# Group12_411_REV0.net
KiCad netlist of a schematic drawn in EAGLE
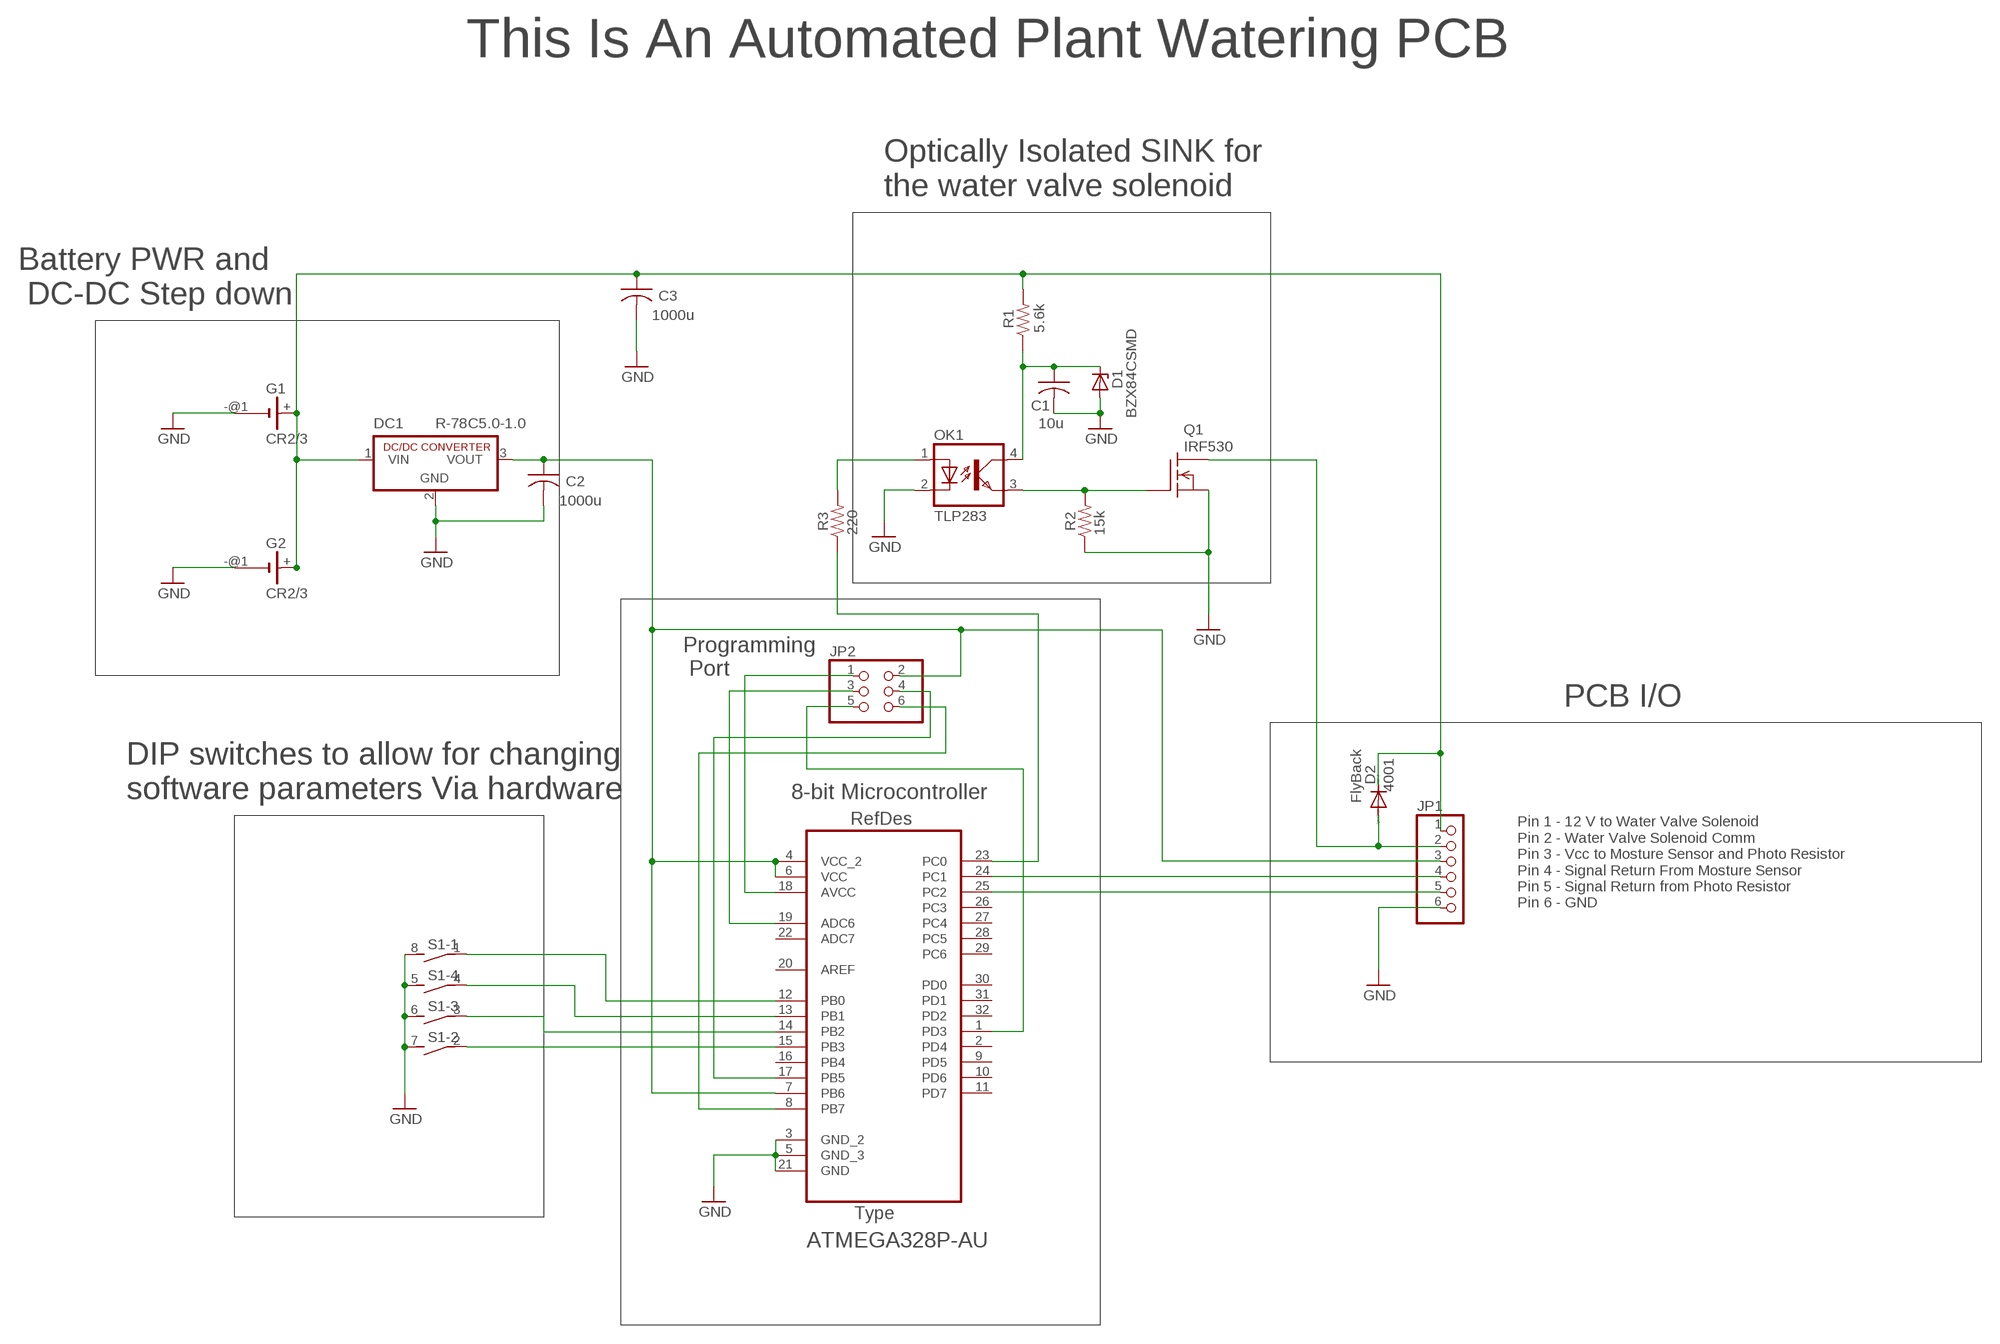
[diagram p0: schematic, sheet 1]

(export (version "E")
  (design (tool "Eeschema 10.0.6"))
  (components
    (comp (ref "ATMEGA328")
      (value "ATMEGA328P-AU")
      (footprint "eagle-import:QFP80P900X900X120-32N")
      (description "8-bit Microcontroller")
      (fields (field (name "MPN") "ATMEGA328P-AU"))
      (libsource (lib "eagle-import") (part "ATMEGA328P-AU"))
    )
    (comp (ref "C1")
      (value "C-USC0805")
      (footprint "eagle-import:C0805")
      (fields (field (name "C") "10u"))
      (libsource (lib "eagle-import") (part "C-USC0805"))
    )
    (comp (ref "C2")
      (value "C-USC0805")
      (footprint "eagle-import:C0805")
      (fields (field (name "C") "1000u"))
      (libsource (lib "eagle-import") (part "C-USC0805"))
    )
    (comp (ref "C3")
      (value "C-USC0805")
      (footprint "eagle-import:C0805")
      (fields (field (name "C") "1000u"))
      (libsource (lib "eagle-import") (part "C-USC0805"))
    )
    (comp (ref "D1")
      (value "BZX84CSMD")
      (footprint "eagle-import:TO236")
      (libsource (lib "eagle-import") (part "BZX84CSMD"))
    )
    (comp (ref "D2")
      (value "ES2D")
      (footprint "eagle-import:SMB")
      (fields (field (name "D") "4001"))
      (libsource (lib "eagle-import") (part "ES2D"))
    )
    (comp (ref "DC1")
      (value "R-78C5.0-1.0")
      (footprint "eagle-import:SIP3")
      (libsource (lib "eagle-import") (part "R-78C-1.05.0"))
    )
    (comp (ref "G1")
      (value "CR2/3")
      (footprint "eagle-import:CR2_3")
      (libsource (lib "eagle-import") (part "CR2/3"))
    )
    (comp (ref "G2")
      (value "CR2/3")
      (footprint "eagle-import:CR2_3")
      (libsource (lib "eagle-import") (part "CR2/3"))
    )
    (comp (ref "JP1")
      (value "PINHD-1X6")
      (footprint "eagle-import:1X06")
      (libsource (lib "eagle-import") (part "PINHD-1X6"))
    )
    (comp (ref "JP2")
      (value "PINHD-2X3")
      (footprint "eagle-import:2X03")
      (libsource (lib "eagle-import") (part "PINHD-2X3"))
    )
    (comp (ref "OK1")
      (value "TLP283")
      (footprint "eagle-import:MINI-FLAT-4")
      (libsource (lib "eagle-import") (part "TLP283"))
    )
    (comp (ref "Q1")
      (value "VN66AF")
      (footprint "eagle-import:TO202")
      (fields (field (name "NPN") "IRF530"))
      (libsource (lib "eagle-import") (part "VN66AF"))
    )
    (comp (ref "R1")
      (value "R-US_M0805")
      (footprint "eagle-import:M0805")
      (fields (field (name "R") "5.6k"))
      (libsource (lib "eagle-import") (part "R-US_M0805"))
    )
    (comp (ref "R2")
      (value "R-US_M0805")
      (footprint "eagle-import:M0805")
      (fields (field (name "R") "15k"))
      (libsource (lib "eagle-import") (part "R-US_M0805"))
    )
    (comp (ref "R3")
      (value "R-US_M0805")
      (footprint "eagle-import:M0805")
      (fields (field (name "R") "220"))
      (libsource (lib "eagle-import") (part "R-US_M0805"))
    )
    (comp (ref "S1")
      (value "DIP04S")
      (footprint "eagle-import:DIP04S")
      (libsource (lib "eagle-import") (part "DIP04S"))
    )
  )
  (nets
    (net (code "1") (name "GND") (class "Default")
      (node (ref "ATMEGA328") (pin "21") (pinfunction "GND_21") (pintype "passive"))
      (node (ref "ATMEGA328") (pin "3") (pinfunction "GND_2_3") (pintype "passive"))
      (node (ref "ATMEGA328") (pin "5") (pinfunction "GND_3_5") (pintype "passive"))
      (node (ref "C1") (pin "2") (pinfunction "2_2") (pintype "passive"))
      (node (ref "C2") (pin "2") (pinfunction "2_2") (pintype "passive"))
      (node (ref "C3") (pin "2") (pinfunction "2_2") (pintype "passive"))
      (node (ref "D1") (pin "A") (pinfunction "A_A") (pintype "passive"))
      (node (ref "DC1") (pin "2") (pinfunction "GND_2") (pintype "passive"))
      (node (ref "G1") (pin "-@1") (pinfunction "-_-@1") (pintype "passive"))
      (node (ref "G2") (pin "-@1") (pinfunction "-_-@1") (pintype "passive"))
      (node (ref "JP1") (pin "6") (pinfunction "6_6") (pintype "passive"))
      (node (ref "OK1") (pin "2") (pinfunction "C_2") (pintype "passive"))
      (node (ref "Q1") (pin "1") (pinfunction "S_1") (pintype "passive"))
      (node (ref "R2") (pin "1") (pinfunction "1_1") (pintype "passive"))
      (node (ref "S1") (pin "5") (pinfunction "2_5") (pintype "passive"))
      (node (ref "S1") (pin "6") (pinfunction "2_6") (pintype "passive"))
      (node (ref "S1") (pin "7") (pinfunction "2_7") (pintype "passive"))
      (node (ref "S1") (pin "8") (pinfunction "2_8") (pintype "passive"))
    )
    (net (code "2") (name "Net-(ATMEGA328-ADC6)") (class "Default")
      (node (ref "ATMEGA328") (pin "19") (pinfunction "ADC6_19") (pintype "input"))
      (node (ref "JP2") (pin "3") (pinfunction "3_3") (pintype "passive"))
    )
    (net (code "3") (name "Net-(ATMEGA328-AVCC)") (class "Default")
      (node (ref "ATMEGA328") (pin "18") (pinfunction "AVCC_18") (pintype "power_in"))
      (node (ref "JP2") (pin "1") (pinfunction "1_1") (pintype "passive"))
    )
    (net (code "4") (name "Net-(ATMEGA328-PB0)") (class "Default")
      (node (ref "ATMEGA328") (pin "12") (pinfunction "PB0_12") (pintype "bidirectional"))
      (node (ref "S1") (pin "1") (pinfunction "1_1") (pintype "passive"))
    )
    (net (code "5") (name "Net-(ATMEGA328-PB1)") (class "Default")
      (node (ref "ATMEGA328") (pin "13") (pinfunction "PB1_13") (pintype "bidirectional"))
      (node (ref "S1") (pin "4") (pinfunction "1_4") (pintype "passive"))
    )
    (net (code "6") (name "Net-(ATMEGA328-PB2)") (class "Default")
      (node (ref "ATMEGA328") (pin "14") (pinfunction "PB2_14") (pintype "bidirectional"))
      (node (ref "S1") (pin "3") (pinfunction "1_3") (pintype "passive"))
    )
    (net (code "7") (name "Net-(ATMEGA328-PB3)") (class "Default")
      (node (ref "ATMEGA328") (pin "15") (pinfunction "PB3_15") (pintype "bidirectional"))
      (node (ref "S1") (pin "2") (pinfunction "1_2") (pintype "passive"))
    )
    (net (code "8") (name "Net-(ATMEGA328-PB5)") (class "Default")
      (node (ref "ATMEGA328") (pin "17") (pinfunction "PB5_17") (pintype "bidirectional"))
      (node (ref "JP2") (pin "4") (pinfunction "4_4") (pintype "passive"))
    )
    (net (code "9") (name "Net-(ATMEGA328-PB6)") (class "Default")
      (node (ref "ATMEGA328") (pin "4") (pinfunction "VCC_2_4") (pintype "power_in"))
      (node (ref "ATMEGA328") (pin "6") (pinfunction "VCC_6") (pintype "power_in"))
      (node (ref "ATMEGA328") (pin "7") (pinfunction "PB6_7") (pintype "bidirectional"))
      (node (ref "C2") (pin "1") (pinfunction "1_1") (pintype "passive"))
      (node (ref "DC1") (pin "3") (pinfunction "VOUT_3") (pintype "passive"))
      (node (ref "JP1") (pin "3") (pinfunction "3_3") (pintype "passive"))
      (node (ref "JP2") (pin "2") (pinfunction "2_2") (pintype "passive"))
    )
    (net (code "10") (name "Net-(ATMEGA328-PB7)") (class "Default")
      (node (ref "ATMEGA328") (pin "8") (pinfunction "PB7_8") (pintype "bidirectional"))
      (node (ref "JP2") (pin "6") (pinfunction "6_6") (pintype "passive"))
    )
    (net (code "11") (name "Net-(ATMEGA328-PC0)") (class "Default")
      (node (ref "ATMEGA328") (pin "23") (pinfunction "PC0_23") (pintype "bidirectional"))
      (node (ref "R3") (pin "1") (pinfunction "1_1") (pintype "passive"))
    )
    (net (code "12") (name "Net-(ATMEGA328-PC1)") (class "Default")
      (node (ref "ATMEGA328") (pin "24") (pinfunction "PC1_24") (pintype "bidirectional"))
      (node (ref "JP1") (pin "4") (pinfunction "4_4") (pintype "passive"))
    )
    (net (code "13") (name "Net-(ATMEGA328-PC2)") (class "Default")
      (node (ref "ATMEGA328") (pin "25") (pinfunction "PC2_25") (pintype "bidirectional"))
      (node (ref "JP1") (pin "5") (pinfunction "5_5") (pintype "passive"))
    )
    (net (code "14") (name "Net-(ATMEGA328-PD3)") (class "Default")
      (node (ref "ATMEGA328") (pin "1") (pinfunction "PD3_1") (pintype "bidirectional"))
      (node (ref "JP2") (pin "5") (pinfunction "5_5") (pintype "passive"))
    )
    (net (code "15") (name "Net-(DC1-VIN)") (class "Default")
      (node (ref "C3") (pin "1") (pinfunction "1_1") (pintype "passive"))
      (node (ref "D2") (pin "C") (pinfunction "C_C") (pintype "passive"))
      (node (ref "DC1") (pin "1") (pinfunction "VIN_1") (pintype "passive"))
      (node (ref "G1") (pin "+") (pinfunction "+_+") (pintype "passive"))
      (node (ref "G2") (pin "+") (pinfunction "+_+") (pintype "passive"))
      (node (ref "JP1") (pin "1") (pinfunction "1_1") (pintype "passive"))
      (node (ref "R1") (pin "2") (pinfunction "2_2") (pintype "passive"))
    )
    (net (code "16") (name "Net-(OK1-A)") (class "Default")
      (node (ref "OK1") (pin "1") (pinfunction "A_1") (pintype "passive"))
      (node (ref "R3") (pin "2") (pinfunction "2_2") (pintype "passive"))
    )
    (net (code "17") (name "Net-(OK1-COL)") (class "Default")
      (node (ref "C1") (pin "1") (pinfunction "1_1") (pintype "passive"))
      (node (ref "D1") (pin "C") (pinfunction "C_C") (pintype "passive"))
      (node (ref "OK1") (pin "4") (pinfunction "COL_4") (pintype "passive"))
      (node (ref "R1") (pin "1") (pinfunction "1_1") (pintype "passive"))
    )
    (net (code "18") (name "Net-(OK1-EMIT)") (class "Default")
      (node (ref "OK1") (pin "3") (pinfunction "EMIT_3") (pintype "passive"))
      (node (ref "Q1") (pin "2") (pinfunction "G_2") (pintype "passive"))
      (node (ref "R2") (pin "2") (pinfunction "2_2") (pintype "passive"))
    )
    (net (code "19") (name "Net-(Q1-D)") (class "Default")
      (node (ref "D2") (pin "A") (pinfunction "A_A") (pintype "passive"))
      (node (ref "JP1") (pin "2") (pinfunction "2_2") (pintype "passive"))
      (node (ref "Q1") (pin "3") (pinfunction "D_3") (pintype "passive"))
    )
    (net (code "20") (name "unconnected-(ATMEGA328-ADC7-Pad22)") (class "Default")
      (node (ref "ATMEGA328") (pin "22") (pinfunction "ADC7_22") (pintype "input"))
    )
    (net (code "21") (name "unconnected-(ATMEGA328-AREF-Pad20)") (class "Default")
      (node (ref "ATMEGA328") (pin "20") (pinfunction "AREF_20") (pintype "input"))
    )
    (net (code "22") (name "unconnected-(ATMEGA328-PB4-Pad16)") (class "Default")
      (node (ref "ATMEGA328") (pin "16") (pinfunction "PB4_16") (pintype "bidirectional"))
    )
    (net (code "23") (name "unconnected-(ATMEGA328-PC3-Pad26)") (class "Default")
      (node (ref "ATMEGA328") (pin "26") (pinfunction "PC3_26") (pintype "bidirectional"))
    )
    (net (code "24") (name "unconnected-(ATMEGA328-PC4-Pad27)") (class "Default")
      (node (ref "ATMEGA328") (pin "27") (pinfunction "PC4_27") (pintype "bidirectional"))
    )
    (net (code "25") (name "unconnected-(ATMEGA328-PC5-Pad28)") (class "Default")
      (node (ref "ATMEGA328") (pin "28") (pinfunction "PC5_28") (pintype "bidirectional"))
    )
    (net (code "26") (name "unconnected-(ATMEGA328-PC6-Pad29)") (class "Default")
      (node (ref "ATMEGA328") (pin "29") (pinfunction "PC6_29") (pintype "bidirectional"))
    )
    (net (code "27") (name "unconnected-(ATMEGA328-PD0-Pad30)") (class "Default")
      (node (ref "ATMEGA328") (pin "30") (pinfunction "PD0_30") (pintype "bidirectional"))
    )
    (net (code "28") (name "unconnected-(ATMEGA328-PD1-Pad31)") (class "Default")
      (node (ref "ATMEGA328") (pin "31") (pinfunction "PD1_31") (pintype "bidirectional"))
    )
    (net (code "29") (name "unconnected-(ATMEGA328-PD2-Pad32)") (class "Default")
      (node (ref "ATMEGA328") (pin "32") (pinfunction "PD2_32") (pintype "bidirectional"))
    )
    (net (code "30") (name "unconnected-(ATMEGA328-PD4-Pad2)") (class "Default")
      (node (ref "ATMEGA328") (pin "2") (pinfunction "PD4_2") (pintype "bidirectional"))
    )
    (net (code "31") (name "unconnected-(ATMEGA328-PD5-Pad9)") (class "Default")
      (node (ref "ATMEGA328") (pin "9") (pinfunction "PD5_9") (pintype "bidirectional"))
    )
    (net (code "32") (name "unconnected-(ATMEGA328-PD6-Pad10)") (class "Default")
      (node (ref "ATMEGA328") (pin "10") (pinfunction "PD6_10") (pintype "bidirectional"))
    )
    (net (code "33") (name "unconnected-(ATMEGA328-PD7-Pad11)") (class "Default")
      (node (ref "ATMEGA328") (pin "11") (pinfunction "PD7_11") (pintype "bidirectional"))
    )
    (net (code "34") (name "unconnected-(G1---Pad-@2)") (class "Default")
      (node (ref "G1") (pin "-@2") (pinfunction "-_-@2") (pintype "passive"))
    )
    (net (code "35") (name "unconnected-(G2---Pad-@2)") (class "Default")
      (node (ref "G2") (pin "-@2") (pinfunction "-_-@2") (pintype "passive"))
    )
  )
)
